# a402-4069-overdrive.net
KiCad netlist of a schematic drawn in EAGLE
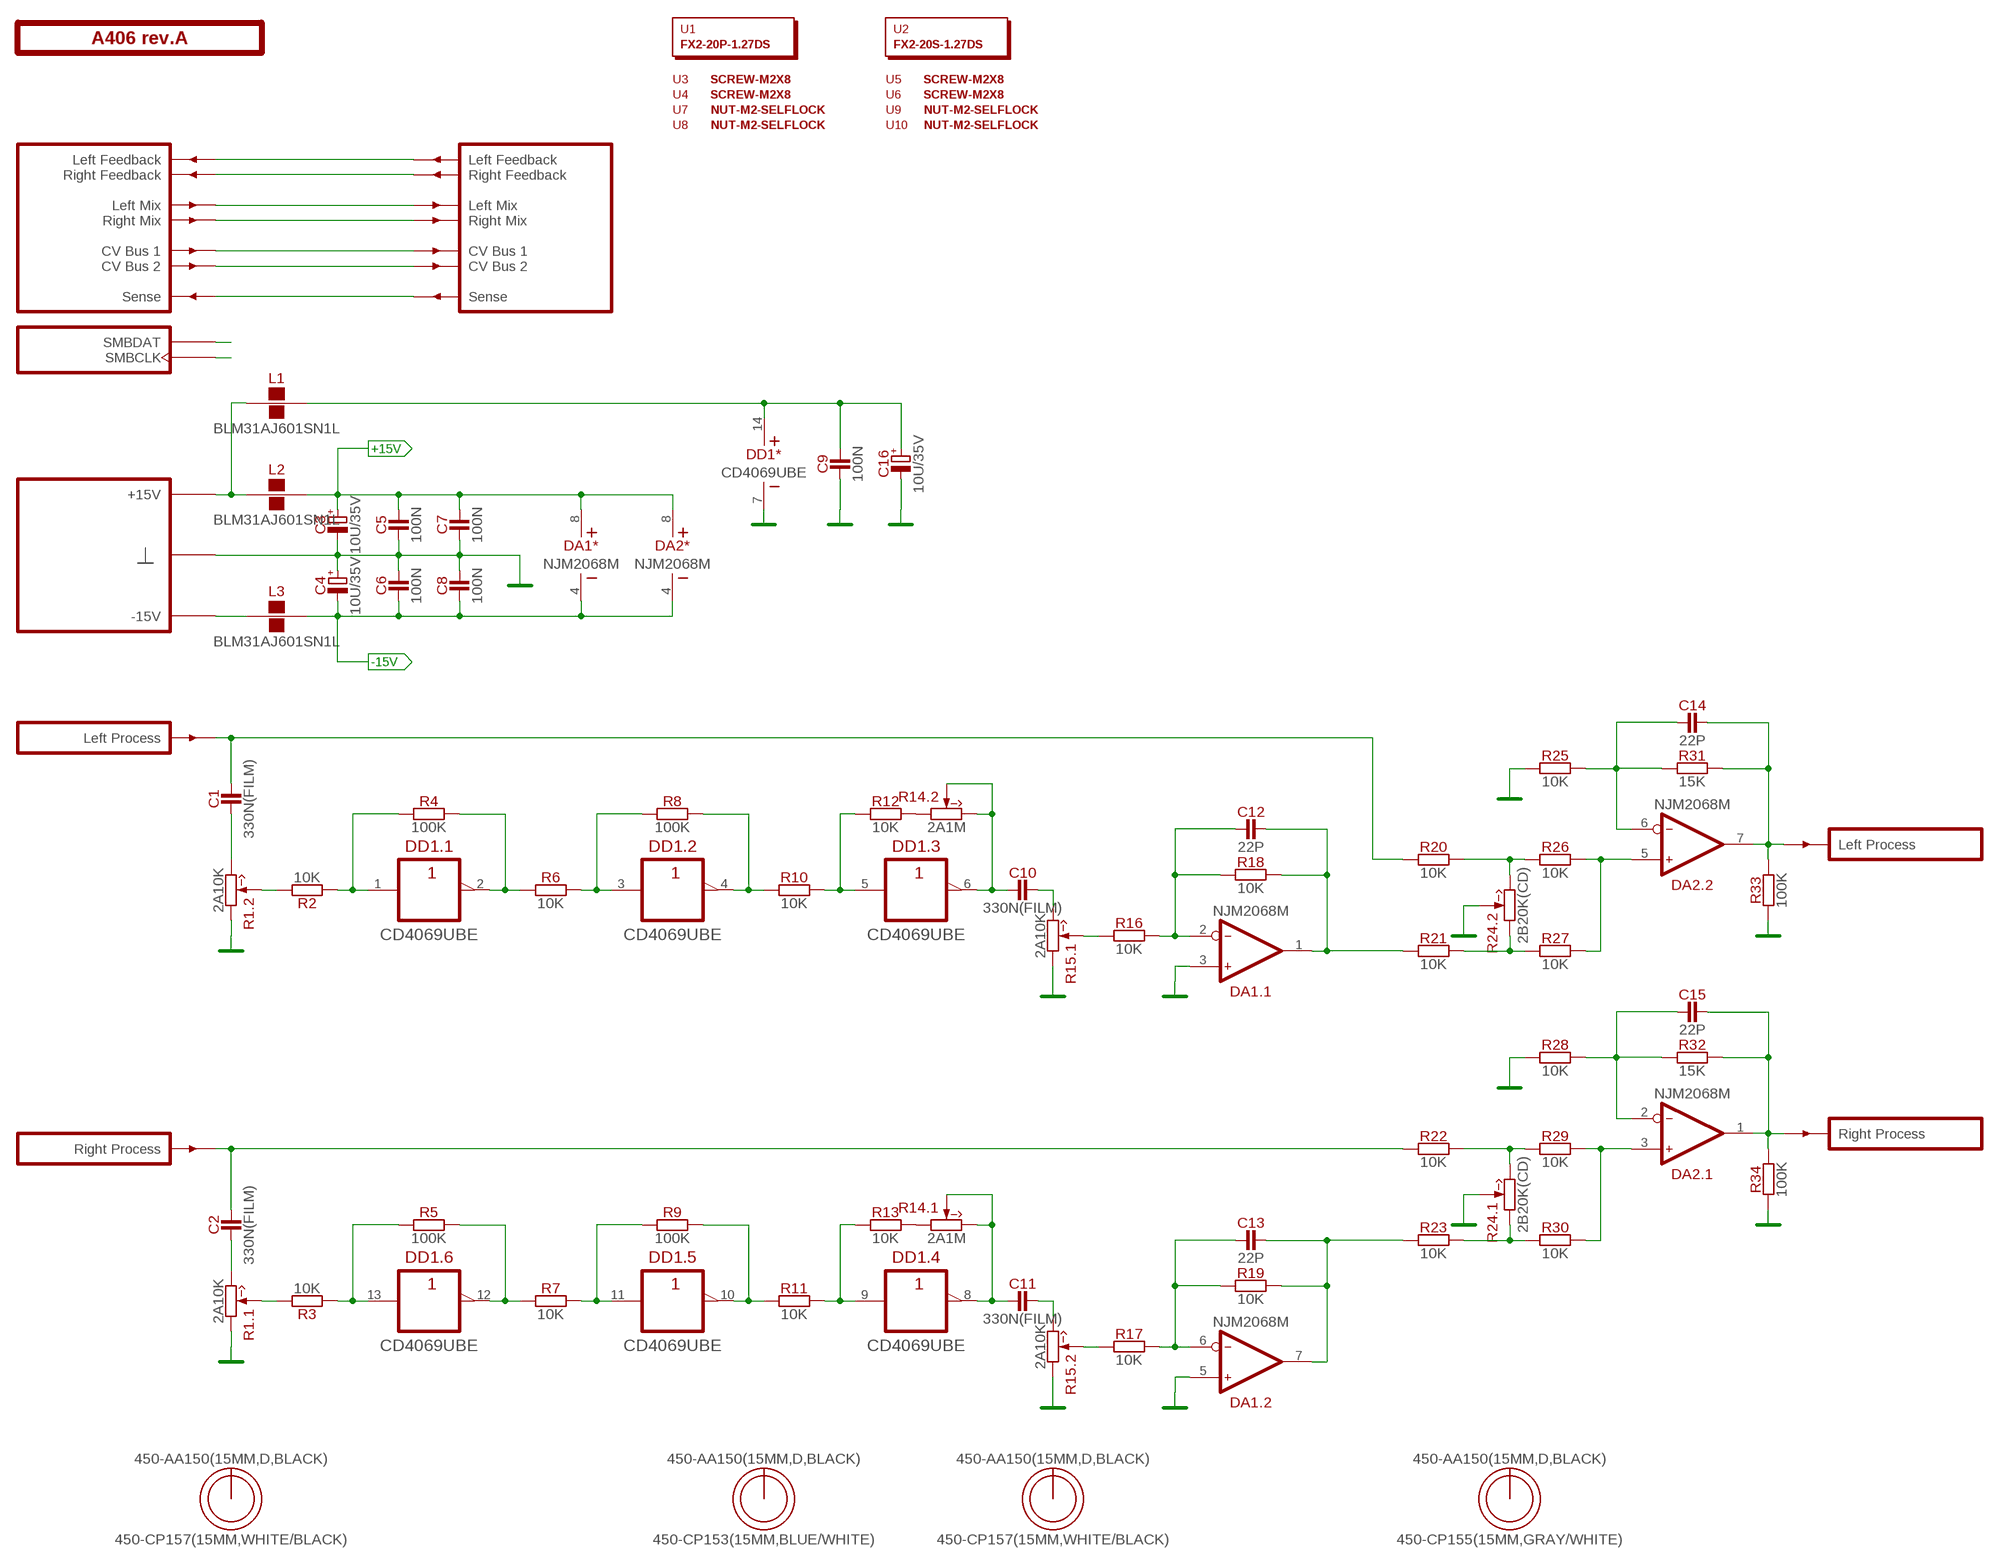
[diagram p0: schematic, sheet 1]

(export (version "E")
  (design (tool "Eeschema 10.0.6"))
  (components
    (comp (ref "C1")
      (value "330N(FILM)")
      (footprint "eagle-import:C050-035X075")
      (libsource (lib "eagle-import") (part "?330N(FILM)"))
    )
    (comp (ref "C2")
      (value "330N(FILM)")
      (footprint "eagle-import:C050-035X075")
      (libsource (lib "eagle-import") (part "?330N(FILM)"))
    )
    (comp (ref "C3")
      (value "10U/35V")
      (footprint "eagle-import:E2-5")
      (libsource (lib "eagle-import") (part "?10U/35V"))
    )
    (comp (ref "C4")
      (value "10U/35V")
      (footprint "eagle-import:E2-5")
      (libsource (lib "eagle-import") (part "?10U/35V"))
    )
    (comp (ref "C5")
      (value "100N")
      (footprint "eagle-import:C-0805")
      (libsource (lib "eagle-import") (part "?100N"))
    )
    (comp (ref "C6")
      (value "100N")
      (footprint "eagle-import:C-0805")
      (libsource (lib "eagle-import") (part "?100N"))
    )
    (comp (ref "C7")
      (value "100N")
      (footprint "eagle-import:C-0805")
      (libsource (lib "eagle-import") (part "?100N"))
    )
    (comp (ref "C8")
      (value "100N")
      (footprint "eagle-import:C-0805")
      (libsource (lib "eagle-import") (part "?100N"))
    )
    (comp (ref "C9")
      (value "100N")
      (footprint "eagle-import:C-0805")
      (libsource (lib "eagle-import") (part "?100N"))
    )
    (comp (ref "C10")
      (value "330N(FILM)")
      (footprint "eagle-import:C050-035X075")
      (libsource (lib "eagle-import") (part "?330N(FILM)"))
    )
    (comp (ref "C11")
      (value "330N(FILM)")
      (footprint "eagle-import:C050-035X075")
      (libsource (lib "eagle-import") (part "?330N(FILM)"))
    )
    (comp (ref "C12")
      (value "22P")
      (footprint "eagle-import:C-0805")
      (libsource (lib "eagle-import") (part "?22P"))
    )
    (comp (ref "C13")
      (value "22P")
      (footprint "eagle-import:C-0805")
      (libsource (lib "eagle-import") (part "?22P"))
    )
    (comp (ref "C14")
      (value "22P")
      (footprint "eagle-import:C-0805")
      (libsource (lib "eagle-import") (part "?22P"))
    )
    (comp (ref "C15")
      (value "22P")
      (footprint "eagle-import:C-0805")
      (libsource (lib "eagle-import") (part "?22P"))
    )
    (comp (ref "C16")
      (value "10U/35V")
      (footprint "eagle-import:E2-5")
      (libsource (lib "eagle-import") (part "?10U/35V"))
    )
    (comp (ref "DA1")
      (value "NJM2068M")
      (footprint "eagle-import:SO-8")
      (libsource (lib "eagle-import") (part "NJM2068M"))
    )
    (comp (ref "DA2")
      (value "NJM2068M")
      (footprint "eagle-import:SO-8")
      (libsource (lib "eagle-import") (part "NJM2068M"))
    )
    (comp (ref "DD1")
      (value "CD4069UBE")
      (footprint "eagle-import:DIP-14")
      (libsource (lib "eagle-import") (part "CD4069UBE"))
    )
    (comp (ref "L1")
      (value "BLM31AJ601SN1L")
      (footprint "eagle-import:1206")
      (libsource (lib "eagle-import") (part "BLM31AJ601SN1L"))
    )
    (comp (ref "L2")
      (value "BLM31AJ601SN1L")
      (footprint "eagle-import:1206")
      (libsource (lib "eagle-import") (part "BLM31AJ601SN1L"))
    )
    (comp (ref "L3")
      (value "BLM31AJ601SN1L")
      (footprint "eagle-import:1206")
      (libsource (lib "eagle-import") (part "BLM31AJ601SN1L"))
    )
    (comp (ref "O2")
      (value "450-AA150(15MM,D,BLACK)")
      (footprint "eagle-import:EMPTY")
      (libsource (lib "eagle-import") (part "450-AA?150(15MM,D,BLACK)"))
    )
    (comp (ref "O3")
      (value "450-CP157(15MM,WHITE/BLACK)")
      (footprint "eagle-import:EMPTY")
      (libsource (lib "eagle-import") (part "450-C?P157(15MM,WHITE/BLACK)"))
    )
    (comp (ref "O4")
      (value "450-AA150(15MM,D,BLACK)")
      (footprint "eagle-import:EMPTY")
      (libsource (lib "eagle-import") (part "450-AA?150(15MM,D,BLACK)"))
    )
    (comp (ref "O5")
      (value "450-CP153(15MM,BLUE/WHITE)")
      (footprint "eagle-import:EMPTY")
      (libsource (lib "eagle-import") (part "450-C?P153(15MM,BLUE/WHITE)"))
    )
    (comp (ref "O6")
      (value "450-AA150(15MM,D,BLACK)")
      (footprint "eagle-import:EMPTY")
      (libsource (lib "eagle-import") (part "450-AA?150(15MM,D,BLACK)"))
    )
    (comp (ref "O7")
      (value "450-CP157(15MM,WHITE/BLACK)")
      (footprint "eagle-import:EMPTY")
      (libsource (lib "eagle-import") (part "450-C?P157(15MM,WHITE/BLACK)"))
    )
    (comp (ref "O8")
      (value "450-AA150(15MM,D,BLACK)")
      (footprint "eagle-import:EMPTY")
      (libsource (lib "eagle-import") (part "450-AA?150(15MM,D,BLACK)"))
    )
    (comp (ref "O9")
      (value "450-CP155(15MM,GRAY/WHITE)")
      (footprint "eagle-import:EMPTY")
      (libsource (lib "eagle-import") (part "450-C?P155(15MM,GRAY/WHITE)"))
    )
    (comp (ref "PCB1")
      (value "A406 rev.A")
      (footprint "eagle-import:ST2-BOARD-50")
      (libsource (lib "eagle-import") (part "ST2-BOARD-?50"))
    )
    (comp (ref "R1")
      (value "2A10K")
      (footprint "eagle-import:RV11-DUAL")
      (libsource (lib "eagle-import") (part "2?A10K"))
    )
    (comp (ref "R2")
      (value "10K")
      (footprint "eagle-import:R-0805")
      (libsource (lib "eagle-import") (part "?10K"))
    )
    (comp (ref "R3")
      (value "10K")
      (footprint "eagle-import:R-0805")
      (libsource (lib "eagle-import") (part "?10K"))
    )
    (comp (ref "R4")
      (value "100K")
      (footprint "eagle-import:R-0805")
      (libsource (lib "eagle-import") (part "?100K"))
    )
    (comp (ref "R5")
      (value "100K")
      (footprint "eagle-import:R-0805")
      (libsource (lib "eagle-import") (part "?100K"))
    )
    (comp (ref "R6")
      (value "10K")
      (footprint "eagle-import:R-0805")
      (libsource (lib "eagle-import") (part "?10K"))
    )
    (comp (ref "R7")
      (value "10K")
      (footprint "eagle-import:R-0805")
      (libsource (lib "eagle-import") (part "?10K"))
    )
    (comp (ref "R8")
      (value "100K")
      (footprint "eagle-import:R-0805")
      (libsource (lib "eagle-import") (part "?100K"))
    )
    (comp (ref "R9")
      (value "100K")
      (footprint "eagle-import:R-0805")
      (libsource (lib "eagle-import") (part "?100K"))
    )
    (comp (ref "R10")
      (value "10K")
      (footprint "eagle-import:R-0805")
      (libsource (lib "eagle-import") (part "?10K"))
    )
    (comp (ref "R11")
      (value "10K")
      (footprint "eagle-import:R-0805")
      (libsource (lib "eagle-import") (part "?10K"))
    )
    (comp (ref "R12")
      (value "10K")
      (footprint "eagle-import:R-0805")
      (libsource (lib "eagle-import") (part "?10K"))
    )
    (comp (ref "R13")
      (value "10K")
      (footprint "eagle-import:R-0805")
      (libsource (lib "eagle-import") (part "?10K"))
    )
    (comp (ref "R14")
      (value "2A1M")
      (footprint "eagle-import:RV11-DUAL")
      (libsource (lib "eagle-import") (part "2?A1M"))
    )
    (comp (ref "R15")
      (value "2A10K")
      (footprint "eagle-import:RV11-DUAL")
      (libsource (lib "eagle-import") (part "2?A10K"))
    )
    (comp (ref "R16")
      (value "10K")
      (footprint "eagle-import:R-0805")
      (libsource (lib "eagle-import") (part "?10K"))
    )
    (comp (ref "R17")
      (value "10K")
      (footprint "eagle-import:R-0805")
      (libsource (lib "eagle-import") (part "?10K"))
    )
    (comp (ref "R18")
      (value "10K")
      (footprint "eagle-import:R-0805")
      (libsource (lib "eagle-import") (part "?10K"))
    )
    (comp (ref "R19")
      (value "10K")
      (footprint "eagle-import:R-0805")
      (libsource (lib "eagle-import") (part "?10K"))
    )
    (comp (ref "R20")
      (value "10K")
      (footprint "eagle-import:R-0805")
      (libsource (lib "eagle-import") (part "?10K"))
    )
    (comp (ref "R21")
      (value "10K")
      (footprint "eagle-import:R-0805")
      (libsource (lib "eagle-import") (part "?10K"))
    )
    (comp (ref "R22")
      (value "10K")
      (footprint "eagle-import:R-0805")
      (libsource (lib "eagle-import") (part "?10K"))
    )
    (comp (ref "R23")
      (value "10K")
      (footprint "eagle-import:R-0805")
      (libsource (lib "eagle-import") (part "?10K"))
    )
    (comp (ref "R24")
      (value "2B20K(CD)")
      (footprint "eagle-import:RV11-DUAL")
      (libsource (lib "eagle-import") (part "2?B20K(CD)"))
    )
    (comp (ref "R25")
      (value "10K")
      (footprint "eagle-import:R-0805")
      (libsource (lib "eagle-import") (part "?10K"))
    )
    (comp (ref "R26")
      (value "10K")
      (footprint "eagle-import:R-0805")
      (libsource (lib "eagle-import") (part "?10K"))
    )
    (comp (ref "R27")
      (value "10K")
      (footprint "eagle-import:R-0805")
      (libsource (lib "eagle-import") (part "?10K"))
    )
    (comp (ref "R28")
      (value "10K")
      (footprint "eagle-import:R-0805")
      (libsource (lib "eagle-import") (part "?10K"))
    )
    (comp (ref "R29")
      (value "10K")
      (footprint "eagle-import:R-0805")
      (libsource (lib "eagle-import") (part "?10K"))
    )
    (comp (ref "R30")
      (value "10K")
      (footprint "eagle-import:R-0805")
      (libsource (lib "eagle-import") (part "?10K"))
    )
    (comp (ref "R31")
      (value "15K")
      (footprint "eagle-import:R-0805")
      (libsource (lib "eagle-import") (part "?15K"))
    )
    (comp (ref "R32")
      (value "15K")
      (footprint "eagle-import:R-0805")
      (libsource (lib "eagle-import") (part "?15K"))
    )
    (comp (ref "R33")
      (value "100K")
      (footprint "eagle-import:R-0805")
      (libsource (lib "eagle-import") (part "?100K"))
    )
    (comp (ref "R34")
      (value "100K")
      (footprint "eagle-import:R-0805")
      (libsource (lib "eagle-import") (part "?100K"))
    )
    (comp (ref "U1")
      (value "FX2-20P-1.27DS")
      (footprint "eagle-import:EMPTY")
      (libsource (lib "eagle-import") (part "?FX2-20P-1.27DS"))
    )
    (comp (ref "U2")
      (value "FX2-20S-1.27DS")
      (footprint "eagle-import:EMPTY")
      (libsource (lib "eagle-import") (part "?FX2-20S-1.27DS"))
    )
    (comp (ref "U3")
      (value "SCREW-M2X8")
      (footprint "eagle-import:EMPTY")
      (libsource (lib "eagle-import") (part "?SCREW-M2X8"))
    )
    (comp (ref "U4")
      (value "SCREW-M2X8")
      (footprint "eagle-import:EMPTY")
      (libsource (lib "eagle-import") (part "?SCREW-M2X8"))
    )
    (comp (ref "U5")
      (value "SCREW-M2X8")
      (footprint "eagle-import:EMPTY")
      (libsource (lib "eagle-import") (part "?SCREW-M2X8"))
    )
    (comp (ref "U6")
      (value "SCREW-M2X8")
      (footprint "eagle-import:EMPTY")
      (libsource (lib "eagle-import") (part "?SCREW-M2X8"))
    )
    (comp (ref "U7")
      (value "NUT-M2-SELFLOCK")
      (footprint "eagle-import:EMPTY")
      (libsource (lib "eagle-import") (part "?NUT-M2-SELFLOCK"))
    )
    (comp (ref "U8")
      (value "NUT-M2-SELFLOCK")
      (footprint "eagle-import:EMPTY")
      (libsource (lib "eagle-import") (part "?NUT-M2-SELFLOCK"))
    )
    (comp (ref "U9")
      (value "NUT-M2-SELFLOCK")
      (footprint "eagle-import:EMPTY")
      (libsource (lib "eagle-import") (part "?NUT-M2-SELFLOCK"))
    )
    (comp (ref "U10")
      (value "NUT-M2-SELFLOCK")
      (footprint "eagle-import:EMPTY")
      (libsource (lib "eagle-import") (part "?NUT-M2-SELFLOCK"))
    )
  )
  (nets
    (net (code "1") (name "+15V") (class "Default")
      (node (ref "C3") (pin "+") (pinfunction "+_+") (pintype "passive"))
      (node (ref "C5") (pin "2") (pinfunction "2_2") (pintype "passive"))
      (node (ref "C7") (pin "2") (pinfunction "2_2") (pintype "passive"))
      (node (ref "DA1") (pin "8") (pinfunction "V+_8") (pintype "power_in"))
      (node (ref "DA2") (pin "8") (pinfunction "V+_8") (pintype "power_in"))
      (node (ref "L2") (pin "2") (pinfunction "2_2") (pintype "passive"))
    )
    (net (code "2") (name "-15V") (class "Default")
      (node (ref "C4") (pin "-") (pinfunction "-_-") (pintype "passive"))
      (node (ref "C6") (pin "1") (pinfunction "1_1") (pintype "passive"))
      (node (ref "C8") (pin "1") (pinfunction "1_1") (pintype "passive"))
      (node (ref "DA1") (pin "4") (pinfunction "V-_4") (pintype "power_in"))
      (node (ref "DA2") (pin "4") (pinfunction "V-_4") (pintype "power_in"))
      (node (ref "L3") (pin "2") (pinfunction "2_2") (pintype "passive"))
    )
    (net (code "3") (name "GND") (class "Default")
      (node (ref "C16") (pin "-") (pinfunction "-_-") (pintype "passive"))
      (node (ref "C3") (pin "-") (pinfunction "-_-") (pintype "passive"))
      (node (ref "C4") (pin "+") (pinfunction "+_+") (pintype "passive"))
      (node (ref "C5") (pin "1") (pinfunction "1_1") (pintype "passive"))
      (node (ref "C6") (pin "2") (pinfunction "2_2") (pintype "passive"))
      (node (ref "C7") (pin "1") (pinfunction "1_1") (pintype "passive"))
      (node (ref "C8") (pin "2") (pinfunction "2_2") (pintype "passive"))
      (node (ref "C9") (pin "1") (pinfunction "1_1") (pintype "passive"))
      (node (ref "DA1") (pin "3") (pinfunction "IN+_3") (pintype "input"))
      (node (ref "DA1") (pin "5") (pinfunction "IN+_5") (pintype "input"))
      (node (ref "DD1") (pin "7") (pinfunction "V-_7") (pintype "power_in"))
      (node (ref "PCB1") (pin "B4") (pinfunction "GND_B4") (pintype "bidirectional"))
      (node (ref "PCB1") (pin "B4'") (pinfunction "GND_B4'") (pintype "bidirectional"))
      (node (ref "PCB1") (pin "B5") (pinfunction "GND_B5") (pintype "bidirectional"))
      (node (ref "PCB1") (pin "B5'") (pinfunction "GND_B5'") (pintype "bidirectional"))
      (node (ref "PCB1") (pin "B6") (pinfunction "GND_B6") (pintype "bidirectional"))
      (node (ref "PCB1") (pin "B6'") (pinfunction "GND_B6'") (pintype "bidirectional"))
      (node (ref "PCB1") (pin "B7") (pinfunction "GND_B7") (pintype "bidirectional"))
      (node (ref "PCB1") (pin "B7'") (pinfunction "GND_B7'") (pintype "bidirectional"))
      (node (ref "PCB1") (pin "B8") (pinfunction "GND_B8") (pintype "bidirectional"))
      (node (ref "PCB1") (pin "B8'") (pinfunction "GND_B8'") (pintype "bidirectional"))
      (node (ref "R1") (pin "1") (pinfunction "CCW_1") (pintype "passive"))
      (node (ref "R1") (pin "1'") (pinfunction "CCW_1'") (pintype "passive"))
      (node (ref "R15") (pin "1") (pinfunction "CCW_1") (pintype "passive"))
      (node (ref "R15") (pin "1'") (pinfunction "CCW_1'") (pintype "passive"))
      (node (ref "R24") (pin "2") (pinfunction "W_2") (pintype "passive"))
      (node (ref "R24") (pin "2'") (pinfunction "W_2'") (pintype "passive"))
      (node (ref "R25") (pin "1") (pinfunction "1_1") (pintype "passive"))
      (node (ref "R28") (pin "1") (pinfunction "1_1") (pintype "passive"))
      (node (ref "R33") (pin "2") (pinfunction "2_2") (pintype "passive"))
      (node (ref "R34") (pin "2") (pinfunction "2_2") (pintype "passive"))
    )
    (net (code "4") (name "Net-(DA1B-IN-)") (class "Default")
      (node (ref "C12") (pin "1") (pinfunction "1_1") (pintype "passive"))
      (node (ref "DA1") (pin "2") (pinfunction "IN-_2") (pintype "input"))
      (node (ref "R16") (pin "2") (pinfunction "2_2") (pintype "passive"))
      (node (ref "R18") (pin "1") (pinfunction "1_1") (pintype "passive"))
    )
    (net (code "5") (name "Net-(DA1B-OUT)") (class "Default")
      (node (ref "C12") (pin "2") (pinfunction "2_2") (pintype "passive"))
      (node (ref "DA1") (pin "1") (pinfunction "OUT_1") (pintype "output"))
      (node (ref "R18") (pin "2") (pinfunction "2_2") (pintype "passive"))
      (node (ref "R21") (pin "1") (pinfunction "1_1") (pintype "passive"))
    )
    (net (code "6") (name "Net-(DA1C-IN-)") (class "Default")
      (node (ref "C13") (pin "1") (pinfunction "1_1") (pintype "passive"))
      (node (ref "DA1") (pin "6") (pinfunction "IN-_6") (pintype "input"))
      (node (ref "R17") (pin "2") (pinfunction "2_2") (pintype "passive"))
      (node (ref "R19") (pin "1") (pinfunction "1_1") (pintype "passive"))
    )
    (net (code "7") (name "Net-(DA1C-OUT)") (class "Default")
      (node (ref "C13") (pin "2") (pinfunction "2_2") (pintype "passive"))
      (node (ref "DA1") (pin "7") (pinfunction "OUT_7") (pintype "output"))
      (node (ref "R19") (pin "2") (pinfunction "2_2") (pintype "passive"))
      (node (ref "R23") (pin "1") (pinfunction "1_1") (pintype "passive"))
    )
    (net (code "8") (name "Net-(DA2B-IN+)") (class "Default")
      (node (ref "DA2") (pin "3") (pinfunction "IN+_3") (pintype "input"))
      (node (ref "R29") (pin "2") (pinfunction "2_2") (pintype "passive"))
      (node (ref "R30") (pin "2") (pinfunction "2_2") (pintype "passive"))
    )
    (net (code "9") (name "Net-(DA2B-IN-)") (class "Default")
      (node (ref "C15") (pin "1") (pinfunction "1_1") (pintype "passive"))
      (node (ref "DA2") (pin "2") (pinfunction "IN-_2") (pintype "input"))
      (node (ref "R28") (pin "2") (pinfunction "2_2") (pintype "passive"))
      (node (ref "R32") (pin "1") (pinfunction "1_1") (pintype "passive"))
    )
    (net (code "10") (name "Net-(DA2B-OUT)") (class "Default")
      (node (ref "C15") (pin "2") (pinfunction "2_2") (pintype "passive"))
      (node (ref "DA2") (pin "1") (pinfunction "OUT_1") (pintype "output"))
      (node (ref "PCB1") (pin "BOUTR'") (pinfunction "OUTR_BOUTR'") (pintype "bidirectional"))
      (node (ref "R32") (pin "2") (pinfunction "2_2") (pintype "passive"))
      (node (ref "R34") (pin "1") (pinfunction "1_1") (pintype "passive"))
    )
    (net (code "11") (name "Net-(DA2C-IN+)") (class "Default")
      (node (ref "DA2") (pin "5") (pinfunction "IN+_5") (pintype "input"))
      (node (ref "R26") (pin "2") (pinfunction "2_2") (pintype "passive"))
      (node (ref "R27") (pin "2") (pinfunction "2_2") (pintype "passive"))
    )
    (net (code "12") (name "Net-(DA2C-IN-)") (class "Default")
      (node (ref "C14") (pin "1") (pinfunction "1_1") (pintype "passive"))
      (node (ref "DA2") (pin "6") (pinfunction "IN-_6") (pintype "input"))
      (node (ref "R25") (pin "2") (pinfunction "2_2") (pintype "passive"))
      (node (ref "R31") (pin "1") (pinfunction "1_1") (pintype "passive"))
    )
    (net (code "13") (name "Net-(DA2C-OUT)") (class "Default")
      (node (ref "C14") (pin "2") (pinfunction "2_2") (pintype "passive"))
      (node (ref "DA2") (pin "7") (pinfunction "OUT_7") (pintype "output"))
      (node (ref "PCB1") (pin "BOUTL'") (pinfunction "OUTL_BOUTL'") (pintype "bidirectional"))
      (node (ref "R31") (pin "2") (pinfunction "2_2") (pintype "passive"))
      (node (ref "R33") (pin "1") (pinfunction "1_1") (pintype "passive"))
    )
    (net (code "14") (name "Net-(DD1A-V+)") (class "Default")
      (node (ref "C16") (pin "+") (pinfunction "+_+") (pintype "passive"))
      (node (ref "C9") (pin "2") (pinfunction "2_2") (pintype "passive"))
      (node (ref "DD1") (pin "14") (pinfunction "V+_14") (pintype "power_in"))
      (node (ref "L1") (pin "2") (pinfunction "2_2") (pintype "passive"))
    )
    (net (code "15") (name "Net-(DD1B-A)") (class "Default")
      (node (ref "DD1") (pin "1") (pinfunction "A_1") (pintype "input"))
      (node (ref "R2") (pin "1") (pinfunction "1_1") (pintype "passive"))
      (node (ref "R4") (pin "1") (pinfunction "1_1") (pintype "passive"))
    )
    (net (code "16") (name "Net-(DD1B-Y)") (class "Default")
      (node (ref "DD1") (pin "2") (pinfunction "Y_2") (pintype "output"))
      (node (ref "R4") (pin "2") (pinfunction "2_2") (pintype "passive"))
      (node (ref "R6") (pin "1") (pinfunction "1_1") (pintype "passive"))
    )
    (net (code "17") (name "Net-(DD1C-A)") (class "Default")
      (node (ref "DD1") (pin "3") (pinfunction "A_3") (pintype "input"))
      (node (ref "R6") (pin "2") (pinfunction "2_2") (pintype "passive"))
      (node (ref "R8") (pin "1") (pinfunction "1_1") (pintype "passive"))
    )
    (net (code "18") (name "Net-(DD1C-Y)") (class "Default")
      (node (ref "DD1") (pin "4") (pinfunction "Y_4") (pintype "output"))
      (node (ref "R10") (pin "1") (pinfunction "1_1") (pintype "passive"))
      (node (ref "R8") (pin "2") (pinfunction "2_2") (pintype "passive"))
    )
    (net (code "19") (name "Net-(DD1D-A)") (class "Default")
      (node (ref "DD1") (pin "5") (pinfunction "A_5") (pintype "input"))
      (node (ref "R10") (pin "2") (pinfunction "2_2") (pintype "passive"))
      (node (ref "R12") (pin "1") (pinfunction "1_1") (pintype "passive"))
    )
    (net (code "20") (name "Net-(DD1D-Y)") (class "Default")
      (node (ref "C10") (pin "1") (pinfunction "1_1") (pintype "passive"))
      (node (ref "DD1") (pin "6") (pinfunction "Y_6") (pintype "output"))
      (node (ref "R14") (pin "2'") (pinfunction "W_2'") (pintype "passive"))
      (node (ref "R14") (pin "3'") (pinfunction "CW_3'") (pintype "passive"))
    )
    (net (code "21") (name "Net-(DD1E-A)") (class "Default")
      (node (ref "DD1") (pin "9") (pinfunction "A_9") (pintype "input"))
      (node (ref "R11") (pin "2") (pinfunction "2_2") (pintype "passive"))
      (node (ref "R13") (pin "1") (pinfunction "1_1") (pintype "passive"))
    )
    (net (code "22") (name "Net-(DD1E-Y)") (class "Default")
      (node (ref "C11") (pin "1") (pinfunction "1_1") (pintype "passive"))
      (node (ref "DD1") (pin "8") (pinfunction "Y_8") (pintype "output"))
      (node (ref "R14") (pin "2") (pinfunction "W_2") (pintype "passive"))
      (node (ref "R14") (pin "3") (pinfunction "CW_3") (pintype "passive"))
    )
    (net (code "23") (name "Net-(DD1F-A)") (class "Default")
      (node (ref "DD1") (pin "11") (pinfunction "A_11") (pintype "input"))
      (node (ref "R7") (pin "2") (pinfunction "2_2") (pintype "passive"))
      (node (ref "R9") (pin "1") (pinfunction "1_1") (pintype "passive"))
    )
    (net (code "24") (name "Net-(DD1F-Y)") (class "Default")
      (node (ref "DD1") (pin "10") (pinfunction "Y_10") (pintype "output"))
      (node (ref "R11") (pin "1") (pinfunction "1_1") (pintype "passive"))
      (node (ref "R9") (pin "2") (pinfunction "2_2") (pintype "passive"))
    )
    (net (code "25") (name "Net-(DD1G-A)") (class "Default")
      (node (ref "DD1") (pin "13") (pinfunction "A_13") (pintype "input"))
      (node (ref "R3") (pin "1") (pinfunction "1_1") (pintype "passive"))
      (node (ref "R5") (pin "1") (pinfunction "1_1") (pintype "passive"))
    )
    (net (code "26") (name "Net-(DD1G-Y)") (class "Default")
      (node (ref "DD1") (pin "12") (pinfunction "Y_12") (pintype "output"))
      (node (ref "R5") (pin "2") (pinfunction "2_2") (pintype "passive"))
      (node (ref "R7") (pin "1") (pinfunction "1_1") (pintype "passive"))
    )
    (net (code "27") (name "Net-(L1-Pad1)") (class "Default")
      (node (ref "L1") (pin "1") (pinfunction "1_1") (pintype "passive"))
      (node (ref "L2") (pin "1") (pinfunction "1_1") (pintype "passive"))
      (node (ref "PCB1") (pin "A+15") (pinfunction "P+15V_A+15") (pintype "bidirectional"))
      (node (ref "PCB1") (pin "A+15'") (pinfunction "P+15V_A+15'") (pintype "bidirectional"))
      (node (ref "PCB1") (pin "B+15") (pinfunction "P+15V_B+15") (pintype "bidirectional"))
      (node (ref "PCB1") (pin "B+15'") (pinfunction "P+15V_B+15'") (pintype "bidirectional"))
    )
    (net (code "28") (name "Net-(L3-Pad1)") (class "Default")
      (node (ref "L3") (pin "1") (pinfunction "1_1") (pintype "passive"))
      (node (ref "PCB1") (pin "A-15") (pinfunction "P-15V_A-15") (pintype "bidirectional"))
      (node (ref "PCB1") (pin "A-15'") (pinfunction "P-15V_A-15'") (pintype "bidirectional"))
      (node (ref "PCB1") (pin "B-15") (pinfunction "P-15V_B-15") (pintype "bidirectional"))
      (node (ref "PCB1") (pin "B-15'") (pinfunction "P-15V_B-15'") (pintype "bidirectional"))
    )
    (net (code "29") (name "Net-(PCB1B-INL)") (class "Default")
      (node (ref "C1") (pin "2") (pinfunction "2_2") (pintype "passive"))
      (node (ref "PCB1") (pin "BINL") (pinfunction "INL_BINL") (pintype "bidirectional"))
      (node (ref "R20") (pin "1") (pinfunction "1_1") (pintype "passive"))
    )
    (net (code "30") (name "Net-(PCB1C-INR)") (class "Default")
      (node (ref "C2") (pin "2") (pinfunction "2_2") (pintype "passive"))
      (node (ref "PCB1") (pin "BINR") (pinfunction "INR_BINR") (pintype "bidirectional"))
      (node (ref "R22") (pin "1") (pinfunction "1_1") (pintype "passive"))
    )
    (net (code "31") (name "Net-(PCB1F-CV1)") (class "Default")
      (node (ref "PCB1") (pin "ACV1") (pinfunction "CV1_ACV1") (pintype "bidirectional"))
      (node (ref "PCB1") (pin "ACV1'") (pinfunction "CV1'_ACV1'") (pintype "bidirectional"))
    )
    (net (code "32") (name "Net-(PCB1F-CV2)") (class "Default")
      (node (ref "PCB1") (pin "ACV2") (pinfunction "CV2_ACV2") (pintype "bidirectional"))
      (node (ref "PCB1") (pin "ACV2'") (pinfunction "CV2'_ACV2'") (pintype "bidirectional"))
    )
    (net (code "33") (name "Net-(PCB1F-LFBK)") (class "Default")
      (node (ref "PCB1") (pin "ALFBK") (pinfunction "LFBK_ALFBK") (pintype "bidirectional"))
      (node (ref "PCB1") (pin "ALFBK'") (pinfunction "LFBK'_ALFBK'") (pintype "bidirectional"))
    )
    (net (code "34") (name "Net-(PCB1F-LMIX)") (class "Default")
      (node (ref "PCB1") (pin "ALMIX") (pinfunction "LMIX_ALMIX") (pintype "bidirectional"))
      (node (ref "PCB1") (pin "ALMIX'") (pinfunction "LMIX'_ALMIX'") (pintype "bidirectional"))
    )
    (net (code "35") (name "Net-(PCB1F-RFBK)") (class "Default")
      (node (ref "PCB1") (pin "ARFBK") (pinfunction "RFBK_ARFBK") (pintype "bidirectional"))
      (node (ref "PCB1") (pin "ARFBK'") (pinfunction "RFBK'_ARFBK'") (pintype "bidirectional"))
    )
    (net (code "36") (name "Net-(PCB1F-RMIX)") (class "Default")
      (node (ref "PCB1") (pin "ARMIX") (pinfunction "RMIX_ARMIX") (pintype "bidirectional"))
      (node (ref "PCB1") (pin "ARMIX'") (pinfunction "RMIX'_ARMIX'") (pintype "bidirectional"))
    )
    (net (code "37") (name "Net-(PCB1F-SENSE)") (class "Default")
      (node (ref "PCB1") (pin "BSENSE") (pinfunction "SENSE_BSENSE") (pintype "bidirectional"))
      (node (ref "PCB1") (pin "BSENSE'") (pinfunction "SENSE'_BSENSE'") (pintype "bidirectional"))
    )
    (net (code "38") (name "Net-(PCB1H-SMBCLK-PadASMBCLK')") (class "Default")
      (node (ref "PCB1") (pin "ASMBCLK") (pinfunction "SMBCLK_ASMBCLK") (pintype "bidirectional"))
      (node (ref "PCB1") (pin "ASMBCLK'") (pinfunction "SMBCLK_ASMBCLK'") (pintype "bidirectional"))
    )
    (net (code "39") (name "Net-(PCB1H-SMBDAT-PadASMBDAT')") (class "Default")
      (node (ref "PCB1") (pin "ASMBDAT") (pinfunction "SMBDAT_ASMBDAT") (pintype "bidirectional"))
      (node (ref "PCB1") (pin "ASMBDAT'") (pinfunction "SMBDAT_ASMBDAT'") (pintype "bidirectional"))
    )
    (net (code "40") (name "Net-(R1A-CW)") (class "Default")
      (node (ref "C2") (pin "1") (pinfunction "1_1") (pintype "passive"))
      (node (ref "R1") (pin "3") (pinfunction "CW_3") (pintype "passive"))
    )
    (net (code "41") (name "Net-(R1A-W)") (class "Default")
      (node (ref "R1") (pin "2") (pinfunction "W_2") (pintype "passive"))
      (node (ref "R3") (pin "2") (pinfunction "2_2") (pintype "passive"))
    )
    (net (code "42") (name "Net-(R1B-CW)") (class "Default")
      (node (ref "C1") (pin "1") (pinfunction "1_1") (pintype "passive"))
      (node (ref "R1") (pin "3'") (pinfunction "CW_3'") (pintype "passive"))
    )
    (net (code "43") (name "Net-(R1B-W)") (class "Default")
      (node (ref "R1") (pin "2'") (pinfunction "W_2'") (pintype "passive"))
      (node (ref "R2") (pin "2") (pinfunction "2_2") (pintype "passive"))
    )
    (net (code "44") (name "Net-(R14A-CCW)") (class "Default")
      (node (ref "R13") (pin "2") (pinfunction "2_2") (pintype "passive"))
      (node (ref "R14") (pin "1") (pinfunction "CCW_1") (pintype "passive"))
    )
    (net (code "45") (name "Net-(R14B-CCW)") (class "Default")
      (node (ref "R12") (pin "2") (pinfunction "2_2") (pintype "passive"))
      (node (ref "R14") (pin "1'") (pinfunction "CCW_1'") (pintype "passive"))
    )
    (net (code "46") (name "Net-(R15A-CW)") (class "Default")
      (node (ref "C10") (pin "2") (pinfunction "2_2") (pintype "passive"))
      (node (ref "R15") (pin "3") (pinfunction "CW_3") (pintype "passive"))
    )
    (net (code "47") (name "Net-(R15A-W)") (class "Default")
      (node (ref "R15") (pin "2") (pinfunction "W_2") (pintype "passive"))
      (node (ref "R16") (pin "1") (pinfunction "1_1") (pintype "passive"))
    )
    (net (code "48") (name "Net-(R15B-CW)") (class "Default")
      (node (ref "C11") (pin "2") (pinfunction "2_2") (pintype "passive"))
      (node (ref "R15") (pin "3'") (pinfunction "CW_3'") (pintype "passive"))
    )
    (net (code "49") (name "Net-(R15B-W)") (class "Default")
      (node (ref "R15") (pin "2'") (pinfunction "W_2'") (pintype "passive"))
      (node (ref "R17") (pin "1") (pinfunction "1_1") (pintype "passive"))
    )
    (net (code "50") (name "Net-(R24A-CCW)") (class "Default")
      (node (ref "R23") (pin "2") (pinfunction "2_2") (pintype "passive"))
      (node (ref "R24") (pin "1") (pinfunction "CCW_1") (pintype "passive"))
      (node (ref "R30") (pin "1") (pinfunction "1_1") (pintype "passive"))
    )
    (net (code "51") (name "Net-(R24A-CW)") (class "Default")
      (node (ref "R22") (pin "2") (pinfunction "2_2") (pintype "passive"))
      (node (ref "R24") (pin "3") (pinfunction "CW_3") (pintype "passive"))
      (node (ref "R29") (pin "1") (pinfunction "1_1") (pintype "passive"))
    )
    (net (code "52") (name "Net-(R24B-CCW)") (class "Default")
      (node (ref "R21") (pin "2") (pinfunction "2_2") (pintype "passive"))
      (node (ref "R24") (pin "1'") (pinfunction "CCW_1'") (pintype "passive"))
      (node (ref "R27") (pin "1") (pinfunction "1_1") (pintype "passive"))
    )
    (net (code "53") (name "Net-(R24B-CW)") (class "Default")
      (node (ref "R20") (pin "2") (pinfunction "2_2") (pintype "passive"))
      (node (ref "R24") (pin "3'") (pinfunction "CW_3'") (pintype "passive"))
      (node (ref "R26") (pin "1") (pinfunction "1_1") (pintype "passive"))
    )
  )
)
